# Power.net
KiCad netlist of a schematic drawn in Altium Designer
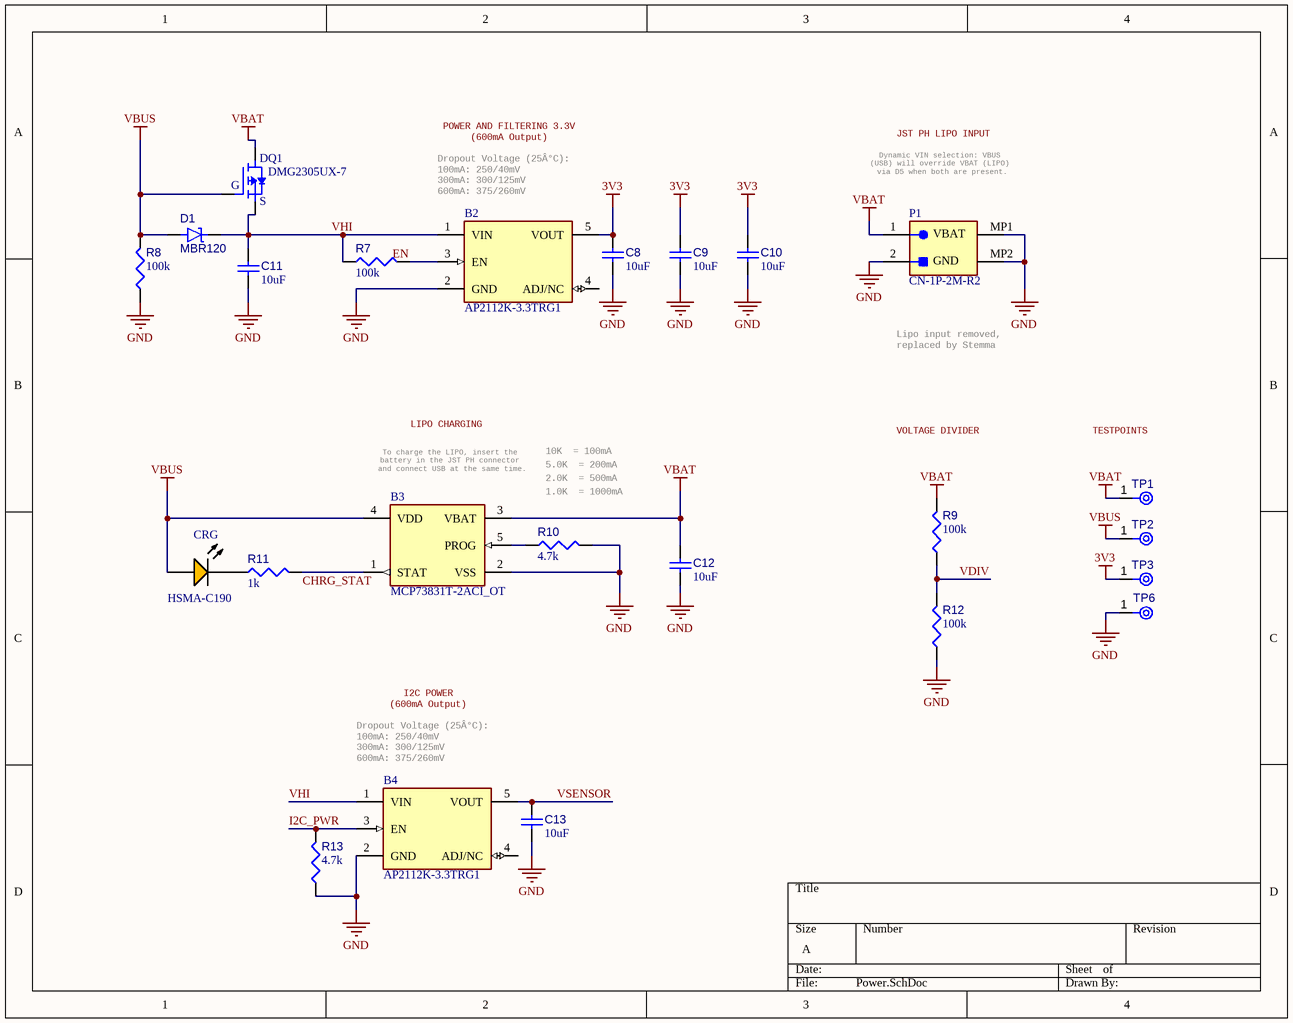
[diagram p0: Power.SchDoc]

(export (version "E")
  (design (tool "Eeschema 10.0.6"))
  (components
    (comp (ref "B2")
      (value "AP2112K-3.3TRG1")
      (footprint "SOT95P270X145-5N")
      (fields (field (name "MOUSER PART NUMBER") "621-AP2112K-3.3TRG1"))
      (libsource (lib "Prototypical Design") (part "AP2112K-3.3TRG1"))
    )
    (comp (ref "B3")
      (value "MCP73831T-2ACI_OT")
      (footprint "SOT95P270X145-5N")
      (description "Li-Ion Charge Controller 4.2V SOT23-5")
      (fields
        (field (name "MOUSER PART NUMBER") "579-MCP73831T-2ACIOT")
        (field (name "MANUFACTURER_PART_NUMBER") "MCP73831T-2ACI/OT")
      )
      (libsource (lib "Prototypical Design") (part "MCP73831T-2ACI_OT"))
    )
    (comp (ref "B4")
      (value "AP2112K-3.3TRG1")
      (footprint "SOT95P270X145-5N")
      (fields (field (name "MOUSER PART NUMBER") "621-AP2112K-3.3TRG1"))
      (libsource (lib "Prototypical Design") (part "AP2112K-3.3TRG1"))
    )
    (comp (ref "C8")
      (value "10uF")
      (footprint "CAPC1608X87X35NL15T15")
      (description "Chip Capacitor, 10 uF, +/- 0.25 uF, 50 V, 0603 (1608 Metric)")
      (fields
        (field (name "TOLERANCE") "0.25%")
        (field (name "Comment") "Capacitor 10 uF +/- 0.25 uF 50 V 0603")
      )
      (libsource (lib "Prototypical Design") (part "CAP-NP-2"))
    )
    (comp (ref "C9")
      (value "10uF")
      (footprint "CAPC1608X87X35NL15T15")
      (description "Chip Capacitor, 10 uF, +/- 0.25 uF, 50 V, 0603 (1608 Metric)")
      (fields
        (field (name "TOLERANCE") "0.25%")
        (field (name "Comment") "Capacitor 10 uF +/- 0.25 uF 50 V 0603")
      )
      (libsource (lib "Prototypical Design") (part "CAP-NP-2"))
    )
    (comp (ref "C10")
      (value "10uF")
      (footprint "CAPC1608X87X35NL15T15")
      (description "Chip Capacitor, 10 uF, +/- 0.25 uF, 50 V, 0603 (1608 Metric)")
      (fields
        (field (name "TOLERANCE") "0.25%")
        (field (name "Comment") "Capacitor 10 uF +/- 0.25 uF 50 V 0603")
      )
      (libsource (lib "Prototypical Design") (part "CAP-NP-2"))
    )
    (comp (ref "C11")
      (value "10uF")
      (footprint "CAPC1608X87X35NL15T15")
      (description "Chip Capacitor, 10 uF, +/- 0.25 uF, 50 V, 0603 (1608 Metric)")
      (fields
        (field (name "TOLERANCE") "0.25%")
        (field (name "Comment") "Capacitor 10 uF +/- 0.25 uF 50 V 0603")
      )
      (libsource (lib "Prototypical Design") (part "CAP-NP-2"))
    )
    (comp (ref "C12")
      (value "10uF")
      (footprint "CAPC1608X87X35NL15T15")
      (description "Chip Capacitor, 10 uF, +/- 0.25 uF, 50 V, 0603 (1608 Metric)")
      (fields
        (field (name "TOLERANCE") "0.25%")
        (field (name "Comment") "Capacitor 10 uF +/- 0.25 uF 50 V 0603")
      )
      (libsource (lib "Prototypical Design") (part "CAP-NP-2"))
    )
    (comp (ref "C13")
      (value "10uF")
      (footprint "CAPC1608X87X35NL15T15")
      (description "Chip Capacitor, 10 uF, +/- 0.25 uF, 50 V, 0603 (1608 Metric)")
      (fields
        (field (name "TOLERANCE") "0.25%")
        (field (name "Comment") "Capacitor 10 uF +/- 0.25 uF 50 V 0603")
      )
      (libsource (lib "Prototypical Design") (part "CAP-NP-2"))
    )
    (comp (ref "CRG")
      (value "HSMA-C190")
      (footprint "AVAG-HSMX-C190_V")
      (description "LED Uni-Color Amber, 60 mW, 20 mA, -40 to 85 degC, 2-Pin SMD, RoHS, Tape and Reel")
      (fields (field (name "POWER") "60mW") (field (name "MANUFACTURER") "Avago"))
      (libsource (lib "Prototypical Design") (part "LED-AMBER-AK-2"))
    )
    (comp (ref "D1")
      (value "MBR120")
      (footprint "ONSC-SOD-123FL-2-498-01_V")
      (description "Diode")
      (libsource (lib "Prototypical Design") (part "MBR120"))
    )
    (comp (ref "P1")
      (value "CN-1P-2M-R2")
      (footprint "JST- S2B-PH-SM4-TB(LF)(SN)-2_V")
      (libsource (lib "Prototypical Design") (part "CN-1P-2M-R2"))
    )
    (comp (ref "Q1")
      (value "DMG2305UX-7")
      (footprint "FP-SOT23-MFG")
      (libsource (lib "Prototypical Design") (part "MOSFET-NPN-3"))
    )
    (comp (ref "R7")
      (value "100k")
      (footprint "RESC1608X55X25ML10T15")
      (description "Chip Resistor, 100 KOhm, +/- 1%, 0.1 W, -55 to 155 degC, 0603 (1608 Metric)")
      (fields (field (name "TOLERANCE") "1%") (field (name "POWER") "100mW"))
      (libsource (lib "Prototypical Design") (part "RES-2"))
    )
    (comp (ref "R8")
      (value "100k")
      (footprint "RESC1608X55X25ML10T15")
      (description "Chip Resistor, 100 KOhm, +/- 1%, 0.1 W, -55 to 155 degC, 0603 (1608 Metric)")
      (fields (field (name "TOLERANCE") "1%") (field (name "POWER") "100mW"))
      (libsource (lib "Prototypical Design") (part "RES-2"))
    )
    (comp (ref "R9")
      (value "100k")
      (footprint "RESC1608X55X25ML10T15")
      (description "Chip Resistor, 100 KOhm, +/- 1%, 0.1 W, -55 to 155 degC, 0603 (1608 Metric)")
      (fields (field (name "TOLERANCE") "1%") (field (name "POWER") "100mW"))
      (libsource (lib "Prototypical Design") (part "RES-2"))
    )
    (comp (ref "R10")
      (value "4.7k")
      (footprint "RESC1608X55X25ML10T15")
      (description "Chip Resistor, 4.7 KOhm, +/- 1%, 0.1 W, -55 to 155 degC, 0603 (1608 Metric)")
      (fields (field (name "TOLERANCE") "1%") (field (name "POWER") "100mW"))
      (libsource (lib "Prototypical Design") (part "RES-2"))
    )
    (comp (ref "R11")
      (value "1k")
      (footprint "RESC1608X55X25ML10T15")
      (description "Chip Resistor, 1 KOhm, +/- 1%, 0.1 W, -55 to 155 degC, 0603 (1608 Metric)")
      (fields (field (name "TOLERANCE") "1%") (field (name "POWER") "100mW"))
      (libsource (lib "Prototypical Design") (part "RES-2"))
    )
    (comp (ref "R12")
      (value "100k")
      (footprint "RESC1608X55X25ML10T15")
      (description "Chip Resistor, 100 KOhm, +/- 1%, 0.1 W, -55 to 155 degC, 0603 (1608 Metric)")
      (fields (field (name "TOLERANCE") "1%") (field (name "POWER") "100mW"))
      (libsource (lib "Prototypical Design") (part "RES-2"))
    )
    (comp (ref "R13")
      (value "4.7k")
      (footprint "RESC1608X55X25ML10T15")
      (description "Chip Resistor, 4.7 KOhm, +/- 1%, 0.1 W, -55 to 155 degC, 0603 (1608 Metric)")
      (fields (field (name "TOLERANCE") "1%") (field (name "POWER") "100mW"))
      (libsource (lib "Prototypical Design") (part "RES-2"))
    )
    (comp (ref "TP1")
      (value "TPAD6R")
      (footprint "TP06R")
      (description "0.6mm round")
      (libsource (lib "McIntyre Industries") (part "CMP-001-0001-4"))
    )
    (comp (ref "TP2")
      (value "TPAD6R")
      (footprint "TP06R")
      (description "0.6mm round")
      (libsource (lib "McIntyre Industries") (part "CMP-001-0001-4"))
    )
    (comp (ref "TP3")
      (value "TPAD6R")
      (footprint "TP06R")
      (description "0.6mm round")
      (libsource (lib "McIntyre Industries") (part "CMP-001-0001-4"))
    )
    (comp (ref "TP6")
      (value "TPAD6R")
      (footprint "TP06R")
      (description "0.6mm round")
      (libsource (lib "McIntyre Industries") (part "CMP-001-0001-4"))
    )
  )
  (nets
    (net (code "1") (name "/CHRG_STAT") (class "Default")
      (node (ref "B3") (pin "1") (pinfunction "STAT_1") (pintype "output"))
      (node (ref "R11") (pin "2") (pinfunction "2_2") (pintype "passive"))
    )
    (net (code "2") (name "/EN") (class "Default")
      (node (ref "B2") (pin "3") (pinfunction "EN_3") (pintype "input"))
      (node (ref "R7") (pin "2") (pinfunction "2_2") (pintype "passive"))
    )
    (net (code "3") (name "/I2C_PWR") (class "Default")
      (node (ref "B4") (pin "3") (pinfunction "EN_3") (pintype "input"))
      (node (ref "R13") (pin "2") (pinfunction "2_2") (pintype "passive"))
    )
    (net (code "4") (name "/VDIV") (class "Default")
      (node (ref "R12") (pin "2") (pinfunction "2_2") (pintype "passive"))
      (node (ref "R9") (pin "1") (pinfunction "1_1") (pintype "passive"))
    )
    (net (code "5") (name "/VHI") (class "Default")
      (node (ref "B2") (pin "1") (pinfunction "VIN_1") (pintype "passive"))
      (node (ref "B4") (pin "1") (pinfunction "VIN_1") (pintype "passive"))
      (node (ref "C11") (pin "2") (pinfunction "2_2") (pintype "passive"))
      (node (ref "D1") (pin "1") (pinfunction "K_1") (pintype "passive"))
      (node (ref "Q1") (pin "2") (pinfunction "S_2") (pintype "passive"))
      (node (ref "R7") (pin "1") (pinfunction "1_1") (pintype "passive"))
    )
    (net (code "6") (name "/VSENSOR") (class "Default")
      (node (ref "B4") (pin "5") (pinfunction "VOUT_5") (pintype "passive"))
      (node (ref "C13") (pin "2") (pinfunction "2_2") (pintype "passive"))
    )
    (net (code "7") (name "3V3") (class "Default")
      (node (ref "B2") (pin "5") (pinfunction "VOUT_5") (pintype "passive"))
      (node (ref "C10") (pin "2") (pinfunction "2_2") (pintype "passive"))
      (node (ref "C8") (pin "2") (pinfunction "2_2") (pintype "passive"))
      (node (ref "C9") (pin "2") (pinfunction "2_2") (pintype "passive"))
      (node (ref "TP3") (pin "1") (pinfunction "TP_1") (pintype "passive"))
    )
    (net (code "8") (name "GND") (class "Default")
      (node (ref "B2") (pin "2") (pinfunction "GND_2") (pintype "passive"))
      (node (ref "B3") (pin "2") (pinfunction "VSS_2") (pintype "passive"))
      (node (ref "B4") (pin "2") (pinfunction "GND_2") (pintype "passive"))
      (node (ref "C10") (pin "1") (pinfunction "1_1") (pintype "passive"))
      (node (ref "C11") (pin "1") (pinfunction "1_1") (pintype "passive"))
      (node (ref "C12") (pin "1") (pinfunction "1_1") (pintype "passive"))
      (node (ref "C13") (pin "1") (pinfunction "1_1") (pintype "passive"))
      (node (ref "C8") (pin "1") (pinfunction "1_1") (pintype "passive"))
      (node (ref "C9") (pin "1") (pinfunction "1_1") (pintype "passive"))
      (node (ref "P1") (pin "2") (pinfunction "2_2") (pintype "passive"))
      (node (ref "P1") (pin "MP1") (pinfunction "MP1_MP1") (pintype "passive"))
      (node (ref "P1") (pin "MP2") (pinfunction "MP2_MP2") (pintype "passive"))
      (node (ref "R10") (pin "2") (pinfunction "2_2") (pintype "passive"))
      (node (ref "R12") (pin "1") (pinfunction "1_1") (pintype "passive"))
      (node (ref "R13") (pin "1") (pinfunction "1_1") (pintype "passive"))
      (node (ref "R8") (pin "1") (pinfunction "1_1") (pintype "passive"))
      (node (ref "TP6") (pin "1") (pinfunction "TP_1") (pintype "passive"))
    )
    (net (code "9") (name "Net-(B3-PROG)") (class "Default")
      (node (ref "B3") (pin "5") (pinfunction "PROG_5") (pintype "input"))
      (node (ref "R10") (pin "1") (pinfunction "1_1") (pintype "passive"))
    )
    (net (code "10") (name "Net-(CRG-K)") (class "Default")
      (node (ref "CRG") (pin "2") (pinfunction "K_2") (pintype "passive"))
      (node (ref "R11") (pin "1") (pinfunction "1_1") (pintype "passive"))
    )
    (net (code "11") (name "VBAT") (class "Default")
      (node (ref "B3") (pin "3") (pinfunction "VBAT_3") (pintype "passive"))
      (node (ref "C12") (pin "2") (pinfunction "2_2") (pintype "passive"))
      (node (ref "P1") (pin "1") (pinfunction "1_1") (pintype "passive"))
      (node (ref "Q1") (pin "3") (pinfunction "D_3") (pintype "passive"))
      (node (ref "R9") (pin "2") (pinfunction "2_2") (pintype "passive"))
      (node (ref "TP1") (pin "1") (pinfunction "TP_1") (pintype "passive"))
    )
    (net (code "12") (name "VBUS") (class "Default")
      (node (ref "B3") (pin "4") (pinfunction "VDD_4") (pintype "passive"))
      (node (ref "CRG") (pin "1") (pinfunction "A_1") (pintype "passive"))
      (node (ref "D1") (pin "2") (pinfunction "A_2") (pintype "passive"))
      (node (ref "Q1") (pin "1") (pinfunction "G_1") (pintype "passive"))
      (node (ref "R8") (pin "2") (pinfunction "2_2") (pintype "passive"))
      (node (ref "TP2") (pin "1") (pinfunction "TP_1") (pintype "passive"))
    )
    (net (code "13") (name "unconnected-(B2-ADJ{slash}NC-Pad4)") (class "Default")
      (node (ref "B2") (pin "4") (pinfunction "ADJ/NC_4") (pintype "bidirectional"))
    )
    (net (code "14") (name "unconnected-(B4-ADJ{slash}NC-Pad4)") (class "Default")
      (node (ref "B4") (pin "4") (pinfunction "ADJ/NC_4") (pintype "bidirectional"))
    )
  )
)
